# cpc_gal_addon_128k.net
KiCad netlist of a schematic drawn in EAGLE
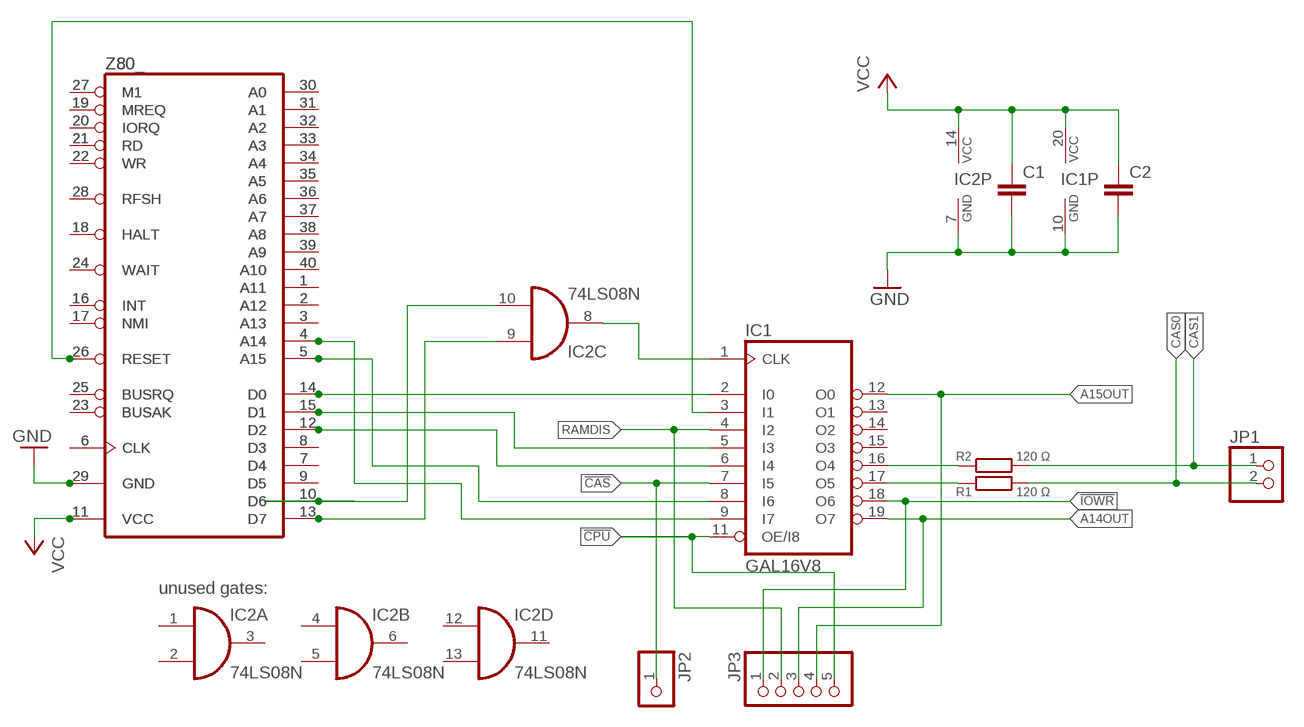
[diagram p0: schematic, sheet 1]

(export (version "E")
  (design (tool "Eeschema 10.0.6"))
  (components
    (comp (ref "C1")
      (value "C-EU025-025X050")
      (footprint "eagle-import:C025-025X050")
      (libsource (lib "eagle-import") (part "C-EU025-025X050"))
    )
    (comp (ref "C2")
      (value "C-EU025-025X050")
      (footprint "eagle-import:C025-025X050")
      (libsource (lib "eagle-import") (part "C-EU025-025X050"))
    )
    (comp (ref "IC1")
      (value "GAL16V8")
      (footprint "eagle-import:DIL20")
      (fields (field (name "MPN") "GAL16V8D-7LPN"))
      (libsource (lib "eagle-import") (part "16V8"))
    )
    (comp (ref "IC2")
      (value "74LS08N")
      (footprint "eagle-import:DIL14")
      (libsource (lib "eagle-import") (part "7408NAC"))
    )
    (comp (ref "JP1")
      (value "PINHD-1X2")
      (footprint "eagle-import:1X02")
      (libsource (lib "eagle-import") (part "PINHD-1X2"))
    )
    (comp (ref "JP2")
      (value "PINHD-1X1")
      (footprint "eagle-import:1X01")
      (libsource (lib "eagle-import") (part "PINHD-1X1"))
    )
    (comp (ref "JP3")
      (value "PINHD-1X5")
      (footprint "eagle-import:1X05")
      (libsource (lib "eagle-import") (part "PINHD-1X5"))
    )
    (comp (ref "R1")
      (value "120 Ω")
      (footprint "eagle-import:0204_5")
      (libsource (lib "eagle-import") (part "R-EU_0204/5"))
    )
    (comp (ref "R2")
      (value "120 Ω")
      (footprint "eagle-import:0204_5")
      (libsource (lib "eagle-import") (part "R-EU_0204/5"))
    )
    (comp (ref "Z80")
      (value "Z80CPU")
      (footprint "eagle-import:DIL40")
      (libsource (lib "eagle-import") (part "Z80CPU"))
    )
    (comp (ref "Z80_")
      (value "Z80CPU")
      (footprint "eagle-import:DIL40")
      (libsource (lib "eagle-import") (part "Z80CPU"))
    )
  )
  (nets
    (net (code "1") (name "/~{CAS}") (class "Default")
      (node (ref "IC1") (pin "7") (pinfunction "I5_7") (pintype "input"))
      (node (ref "JP2") (pin "1") (pinfunction "1_1") (pintype "passive"))
    )
    (net (code "2") (name "/~{CPU}") (class "Default")
      (node (ref "IC1") (pin "11") (pinfunction "OE/I8_11") (pintype "input"))
      (node (ref "JP3") (pin "5") (pinfunction "5_5") (pintype "passive"))
    )
    (net (code "3") (name "/~{IOWR}") (class "Default")
      (node (ref "IC1") (pin "18") (pinfunction "O6_18") (pintype "bidirectional"))
      (node (ref "JP3") (pin "1") (pinfunction "1_1") (pintype "passive"))
    )
    (net (code "4") (name "A14OUT") (class "Default")
      (node (ref "IC1") (pin "19") (pinfunction "O7_19") (pintype "bidirectional"))
      (node (ref "JP3") (pin "3") (pinfunction "3_3") (pintype "passive"))
    )
    (net (code "5") (name "A15OUT") (class "Default")
      (node (ref "IC1") (pin "12") (pinfunction "O0_12") (pintype "bidirectional"))
      (node (ref "JP3") (pin "4") (pinfunction "4_4") (pintype "passive"))
    )
    (net (code "6") (name "CAS0") (class "Default")
      (node (ref "JP1") (pin "2") (pinfunction "2_2") (pintype "passive"))
      (node (ref "R1") (pin "2") (pinfunction "2_2") (pintype "passive"))
    )
    (net (code "7") (name "CAS1") (class "Default")
      (node (ref "JP1") (pin "1") (pinfunction "1_1") (pintype "passive"))
      (node (ref "R2") (pin "2") (pinfunction "2_2") (pintype "passive"))
    )
    (net (code "8") (name "GND") (class "Default")
      (node (ref "C1") (pin "2") (pinfunction "2_2") (pintype "passive"))
      (node (ref "C2") (pin "2") (pinfunction "2_2") (pintype "passive"))
      (node (ref "IC1") (pin "10") (pinfunction "GND_10") (pintype "power_in"))
      (node (ref "IC2") (pin "7") (pinfunction "GND_7") (pintype "power_in"))
      (node (ref "Z80") (pin "29") (pinfunction "GND_29") (pintype "power_in"))
      (node (ref "Z80_") (pin "29") (pinfunction "GND_29") (pintype "power_in"))
    )
    (net (code "9") (name "Net-(IC1A-CLK)") (class "Default")
      (node (ref "IC1") (pin "1") (pinfunction "CLK_1") (pintype "input"))
      (node (ref "IC2") (pin "8") (pinfunction "O_8") (pintype "output"))
    )
    (net (code "10") (name "Net-(IC1A-I0)") (class "Default")
      (node (ref "IC1") (pin "2") (pinfunction "I0_2") (pintype "input"))
      (node (ref "Z80") (pin "14") (pinfunction "D0_14") (pintype "bidirectional"))
      (node (ref "Z80_") (pin "14") (pinfunction "D0_14") (pintype "bidirectional"))
    )
    (net (code "11") (name "Net-(IC1A-I1)") (class "Default")
      (node (ref "IC1") (pin "3") (pinfunction "I1_3") (pintype "input"))
      (node (ref "Z80") (pin "26") (pinfunction "RESET_26") (pintype "input"))
      (node (ref "Z80_") (pin "26") (pinfunction "RESET_26") (pintype "input"))
    )
    (net (code "12") (name "Net-(IC1A-I3)") (class "Default")
      (node (ref "IC1") (pin "5") (pinfunction "I3_5") (pintype "input"))
      (node (ref "Z80") (pin "15") (pinfunction "D1_15") (pintype "bidirectional"))
      (node (ref "Z80_") (pin "15") (pinfunction "D1_15") (pintype "bidirectional"))
    )
    (net (code "13") (name "Net-(IC1A-I4)") (class "Default")
      (node (ref "IC1") (pin "6") (pinfunction "I4_6") (pintype "input"))
      (node (ref "Z80") (pin "12") (pinfunction "D2_12") (pintype "bidirectional"))
      (node (ref "Z80_") (pin "12") (pinfunction "D2_12") (pintype "bidirectional"))
    )
    (net (code "14") (name "Net-(IC1A-I6)") (class "Default")
      (node (ref "IC1") (pin "8") (pinfunction "I6_8") (pintype "input"))
      (node (ref "Z80") (pin "5") (pinfunction "A15_5") (pintype "output"))
      (node (ref "Z80_") (pin "5") (pinfunction "A15_5") (pintype "output"))
    )
    (net (code "15") (name "Net-(IC1A-I7)") (class "Default")
      (node (ref "IC1") (pin "9") (pinfunction "I7_9") (pintype "input"))
      (node (ref "Z80") (pin "4") (pinfunction "A14_4") (pintype "output"))
      (node (ref "Z80_") (pin "4") (pinfunction "A14_4") (pintype "output"))
    )
    (net (code "16") (name "Net-(IC1A-O4)") (class "Default")
      (node (ref "IC1") (pin "16") (pinfunction "O4_16") (pintype "bidirectional"))
      (node (ref "R2") (pin "1") (pinfunction "1_1") (pintype "passive"))
    )
    (net (code "17") (name "Net-(IC1A-O5)") (class "Default")
      (node (ref "IC1") (pin "17") (pinfunction "O5_17") (pintype "bidirectional"))
      (node (ref "R1") (pin "1") (pinfunction "1_1") (pintype "passive"))
    )
    (net (code "18") (name "Net-(IC2C-I0)") (class "Default")
      (node (ref "IC2") (pin "9") (pinfunction "I0_9") (pintype "input"))
      (node (ref "Z80") (pin "13") (pinfunction "D7_13") (pintype "bidirectional"))
      (node (ref "Z80_") (pin "13") (pinfunction "D7_13") (pintype "bidirectional"))
    )
    (net (code "19") (name "Net-(IC2C-I1)") (class "Default")
      (node (ref "IC2") (pin "10") (pinfunction "I1_10") (pintype "input"))
      (node (ref "Z80") (pin "10") (pinfunction "D6_10") (pintype "bidirectional"))
      (node (ref "Z80_") (pin "10") (pinfunction "D6_10") (pintype "bidirectional"))
    )
    (net (code "20") (name "Net-(Z80-A0)") (class "Default")
      (node (ref "Z80") (pin "30") (pinfunction "A0_30") (pintype "output"))
      (node (ref "Z80_") (pin "30") (pinfunction "A0_30") (pintype "output"))
    )
    (net (code "21") (name "Net-(Z80-A1)") (class "Default")
      (node (ref "Z80") (pin "31") (pinfunction "A1_31") (pintype "output"))
      (node (ref "Z80_") (pin "31") (pinfunction "A1_31") (pintype "output"))
    )
    (net (code "22") (name "Net-(Z80-A2)") (class "Default")
      (node (ref "Z80") (pin "32") (pinfunction "A2_32") (pintype "output"))
      (node (ref "Z80_") (pin "32") (pinfunction "A2_32") (pintype "output"))
    )
    (net (code "23") (name "Net-(Z80-A3)") (class "Default")
      (node (ref "Z80") (pin "33") (pinfunction "A3_33") (pintype "output"))
      (node (ref "Z80_") (pin "33") (pinfunction "A3_33") (pintype "output"))
    )
    (net (code "24") (name "Net-(Z80-A4)") (class "Default")
      (node (ref "Z80") (pin "34") (pinfunction "A4_34") (pintype "output"))
      (node (ref "Z80_") (pin "34") (pinfunction "A4_34") (pintype "output"))
    )
    (net (code "25") (name "Net-(Z80-A5)") (class "Default")
      (node (ref "Z80") (pin "35") (pinfunction "A5_35") (pintype "output"))
      (node (ref "Z80_") (pin "35") (pinfunction "A5_35") (pintype "output"))
    )
    (net (code "26") (name "Net-(Z80-A6)") (class "Default")
      (node (ref "Z80") (pin "36") (pinfunction "A6_36") (pintype "output"))
      (node (ref "Z80_") (pin "36") (pinfunction "A6_36") (pintype "output"))
    )
    (net (code "27") (name "Net-(Z80-A7)") (class "Default")
      (node (ref "Z80") (pin "37") (pinfunction "A7_37") (pintype "output"))
      (node (ref "Z80_") (pin "37") (pinfunction "A7_37") (pintype "output"))
    )
    (net (code "28") (name "Net-(Z80-A8)") (class "Default")
      (node (ref "Z80") (pin "38") (pinfunction "A8_38") (pintype "output"))
      (node (ref "Z80_") (pin "38") (pinfunction "A8_38") (pintype "output"))
    )
    (net (code "29") (name "Net-(Z80-A9)") (class "Default")
      (node (ref "Z80") (pin "39") (pinfunction "A9_39") (pintype "output"))
      (node (ref "Z80_") (pin "39") (pinfunction "A9_39") (pintype "output"))
    )
    (net (code "30") (name "Net-(Z80-A10)") (class "Default")
      (node (ref "Z80") (pin "40") (pinfunction "A10_40") (pintype "output"))
      (node (ref "Z80_") (pin "40") (pinfunction "A10_40") (pintype "output"))
    )
    (net (code "31") (name "Net-(Z80-A11)") (class "Default")
      (node (ref "Z80") (pin "1") (pinfunction "A11_1") (pintype "output"))
      (node (ref "Z80_") (pin "1") (pinfunction "A11_1") (pintype "output"))
    )
    (net (code "32") (name "Net-(Z80-A12)") (class "Default")
      (node (ref "Z80") (pin "2") (pinfunction "A12_2") (pintype "output"))
      (node (ref "Z80_") (pin "2") (pinfunction "A12_2") (pintype "output"))
    )
    (net (code "33") (name "Net-(Z80-A13)") (class "Default")
      (node (ref "Z80") (pin "3") (pinfunction "A13_3") (pintype "output"))
      (node (ref "Z80_") (pin "3") (pinfunction "A13_3") (pintype "output"))
    )
    (net (code "34") (name "Net-(Z80-BUSAK)") (class "Default")
      (node (ref "Z80") (pin "23") (pinfunction "BUSAK_23") (pintype "output"))
      (node (ref "Z80_") (pin "23") (pinfunction "BUSAK_23") (pintype "output"))
    )
    (net (code "35") (name "Net-(Z80-BUSRQ)") (class "Default")
      (node (ref "Z80") (pin "25") (pinfunction "BUSRQ_25") (pintype "input"))
      (node (ref "Z80_") (pin "25") (pinfunction "BUSRQ_25") (pintype "input"))
    )
    (net (code "36") (name "Net-(Z80-CLK)") (class "Default")
      (node (ref "Z80") (pin "6") (pinfunction "CLK_6") (pintype "input"))
      (node (ref "Z80_") (pin "6") (pinfunction "CLK_6") (pintype "input"))
    )
    (net (code "37") (name "Net-(Z80-D3)") (class "Default")
      (node (ref "Z80") (pin "8") (pinfunction "D3_8") (pintype "bidirectional"))
      (node (ref "Z80_") (pin "8") (pinfunction "D3_8") (pintype "bidirectional"))
    )
    (net (code "38") (name "Net-(Z80-D4)") (class "Default")
      (node (ref "Z80") (pin "7") (pinfunction "D4_7") (pintype "bidirectional"))
      (node (ref "Z80_") (pin "7") (pinfunction "D4_7") (pintype "bidirectional"))
    )
    (net (code "39") (name "Net-(Z80-D5)") (class "Default")
      (node (ref "Z80") (pin "9") (pinfunction "D5_9") (pintype "bidirectional"))
      (node (ref "Z80_") (pin "9") (pinfunction "D5_9") (pintype "bidirectional"))
    )
    (net (code "40") (name "Net-(Z80-HALT)") (class "Default")
      (node (ref "Z80") (pin "18") (pinfunction "HALT_18") (pintype "output"))
      (node (ref "Z80_") (pin "18") (pinfunction "HALT_18") (pintype "output"))
    )
    (net (code "41") (name "Net-(Z80-INT)") (class "Default")
      (node (ref "Z80") (pin "16") (pinfunction "INT_16") (pintype "input"))
      (node (ref "Z80_") (pin "16") (pinfunction "INT_16") (pintype "input"))
    )
    (net (code "42") (name "Net-(Z80-IORQ)") (class "Default")
      (node (ref "Z80") (pin "20") (pinfunction "IORQ_20") (pintype "output"))
      (node (ref "Z80_") (pin "20") (pinfunction "IORQ_20") (pintype "output"))
    )
    (net (code "43") (name "Net-(Z80-M1)") (class "Default")
      (node (ref "Z80") (pin "27") (pinfunction "M1_27") (pintype "output"))
      (node (ref "Z80_") (pin "27") (pinfunction "M1_27") (pintype "output"))
    )
    (net (code "44") (name "Net-(Z80-MREQ)") (class "Default")
      (node (ref "Z80") (pin "19") (pinfunction "MREQ_19") (pintype "output"))
      (node (ref "Z80_") (pin "19") (pinfunction "MREQ_19") (pintype "output"))
    )
    (net (code "45") (name "Net-(Z80-NMI)") (class "Default")
      (node (ref "Z80") (pin "17") (pinfunction "NMI_17") (pintype "input"))
      (node (ref "Z80_") (pin "17") (pinfunction "NMI_17") (pintype "input"))
    )
    (net (code "46") (name "Net-(Z80-RD)") (class "Default")
      (node (ref "Z80") (pin "21") (pinfunction "RD_21") (pintype "output"))
      (node (ref "Z80_") (pin "21") (pinfunction "RD_21") (pintype "output"))
    )
    (net (code "47") (name "Net-(Z80-RFSH)") (class "Default")
      (node (ref "Z80") (pin "28") (pinfunction "RFSH_28") (pintype "output"))
      (node (ref "Z80_") (pin "28") (pinfunction "RFSH_28") (pintype "output"))
    )
    (net (code "48") (name "Net-(Z80-WAIT)") (class "Default")
      (node (ref "Z80") (pin "24") (pinfunction "WAIT_24") (pintype "input"))
      (node (ref "Z80_") (pin "24") (pinfunction "WAIT_24") (pintype "input"))
    )
    (net (code "49") (name "Net-(Z80-WR)") (class "Default")
      (node (ref "Z80") (pin "22") (pinfunction "WR_22") (pintype "output"))
      (node (ref "Z80_") (pin "22") (pinfunction "WR_22") (pintype "output"))
    )
    (net (code "50") (name "RAMDIS") (class "Default")
      (node (ref "IC1") (pin "4") (pinfunction "I2_4") (pintype "input"))
      (node (ref "JP3") (pin "2") (pinfunction "2_2") (pintype "passive"))
    )
    (net (code "51") (name "VCC") (class "Default")
      (node (ref "C1") (pin "1") (pinfunction "1_1") (pintype "passive"))
      (node (ref "C2") (pin "1") (pinfunction "1_1") (pintype "passive"))
      (node (ref "IC1") (pin "20") (pinfunction "VCC_20") (pintype "power_in"))
      (node (ref "IC2") (pin "14") (pinfunction "VCC_14") (pintype "power_in"))
      (node (ref "Z80") (pin "11") (pinfunction "VCC_11") (pintype "power_in"))
      (node (ref "Z80_") (pin "11") (pinfunction "VCC_11") (pintype "power_in"))
    )
    (net (code "52") (name "unconnected-(IC1A-O1-Pad13)") (class "Default")
      (node (ref "IC1") (pin "13") (pinfunction "O1_13") (pintype "bidirectional"))
    )
    (net (code "53") (name "unconnected-(IC1A-O2-Pad14)") (class "Default")
      (node (ref "IC1") (pin "14") (pinfunction "O2_14") (pintype "bidirectional"))
    )
    (net (code "54") (name "unconnected-(IC1A-O3-Pad15)") (class "Default")
      (node (ref "IC1") (pin "15") (pinfunction "O3_15") (pintype "bidirectional"))
    )
    (net (code "55") (name "unconnected-(IC2A-I0-Pad1)") (class "Default")
      (node (ref "IC2") (pin "1") (pinfunction "I0_1") (pintype "input"))
    )
    (net (code "56") (name "unconnected-(IC2A-I1-Pad2)") (class "Default")
      (node (ref "IC2") (pin "2") (pinfunction "I1_2") (pintype "input"))
    )
    (net (code "57") (name "unconnected-(IC2A-O-Pad3)") (class "Default")
      (node (ref "IC2") (pin "3") (pinfunction "O_3") (pintype "output"))
    )
    (net (code "58") (name "unconnected-(IC2B-I0-Pad4)") (class "Default")
      (node (ref "IC2") (pin "4") (pinfunction "I0_4") (pintype "input"))
    )
    (net (code "59") (name "unconnected-(IC2B-I1-Pad5)") (class "Default")
      (node (ref "IC2") (pin "5") (pinfunction "I1_5") (pintype "input"))
    )
    (net (code "60") (name "unconnected-(IC2B-O-Pad6)") (class "Default")
      (node (ref "IC2") (pin "6") (pinfunction "O_6") (pintype "output"))
    )
    (net (code "61") (name "unconnected-(IC2D-I0-Pad12)") (class "Default")
      (node (ref "IC2") (pin "12") (pinfunction "I0_12") (pintype "input"))
    )
    (net (code "62") (name "unconnected-(IC2D-I1-Pad13)") (class "Default")
      (node (ref "IC2") (pin "13") (pinfunction "I1_13") (pintype "input"))
    )
    (net (code "63") (name "unconnected-(IC2D-O-Pad11)") (class "Default")
      (node (ref "IC2") (pin "11") (pinfunction "O_11") (pintype "output"))
    )
  )
)
